# Filter_Capacitors_-_Port_A.net
KiCad netlist of a schematic drawn in Altium Designer
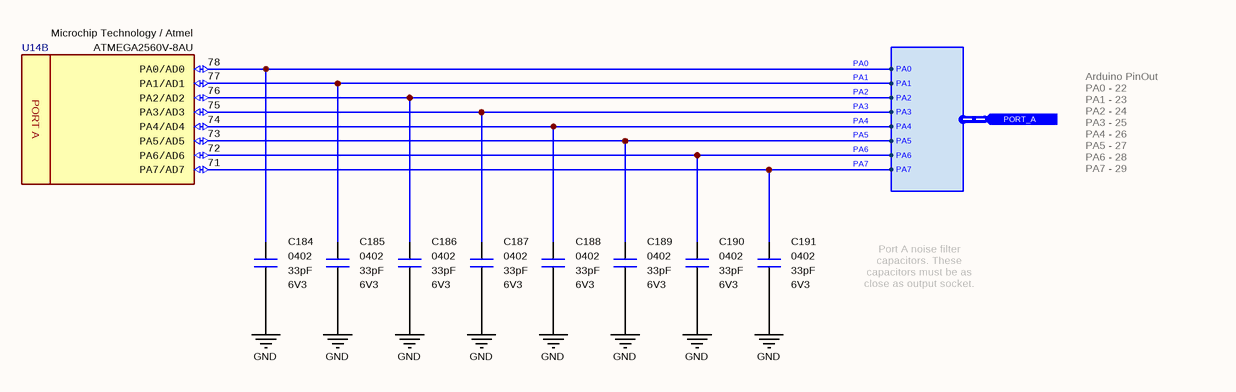
[diagram p0: Filter Capacitors - Port A.SchDoc]

(export (version "E")
  (design (tool "Eeschema 10.0.6"))
  (components
    (comp (ref "C184")
      (value "33pF")
      (footprint "CAPACITOR_0402")
      (description "Capacitor - 33pF [0402] (Ceramic)")
      (fields
        (field (name "TOLERANCE") "10%")
        (field (name "CASE") "0402")
        (field (name "VOLTAGE") "6V3")
        (field (name "MANUFACTURER PART NUMBER") "C0402C330J9RACAUTO")
      )
      (libsource (lib "Ovoo_Library") (part "Capacitor - 33pF [0402-6V3]"))
    )
    (comp (ref "C185")
      (value "33pF")
      (footprint "CAPACITOR_0402")
      (description "Capacitor - 33pF [0402] (Ceramic)")
      (fields
        (field (name "TOLERANCE") "10%")
        (field (name "CASE") "0402")
        (field (name "VOLTAGE") "6V3")
        (field (name "MANUFACTURER PART NUMBER") "C0402C330J9RACAUTO")
      )
      (libsource (lib "Ovoo_Library") (part "Capacitor - 33pF [0402-6V3]"))
    )
    (comp (ref "C186")
      (value "33pF")
      (footprint "CAPACITOR_0402")
      (description "Capacitor - 33pF [0402] (Ceramic)")
      (fields
        (field (name "TOLERANCE") "10%")
        (field (name "CASE") "0402")
        (field (name "VOLTAGE") "6V3")
        (field (name "MANUFACTURER PART NUMBER") "C0402C330J9RACAUTO")
      )
      (libsource (lib "Ovoo_Library") (part "Capacitor - 33pF [0402-6V3]"))
    )
    (comp (ref "C187")
      (value "33pF")
      (footprint "CAPACITOR_0402")
      (description "Capacitor - 33pF [0402] (Ceramic)")
      (fields
        (field (name "TOLERANCE") "10%")
        (field (name "CASE") "0402")
        (field (name "VOLTAGE") "6V3")
        (field (name "MANUFACTURER PART NUMBER") "C0402C330J9RACAUTO")
      )
      (libsource (lib "Ovoo_Library") (part "Capacitor - 33pF [0402-6V3]"))
    )
    (comp (ref "C188")
      (value "33pF")
      (footprint "CAPACITOR_0402")
      (description "Capacitor - 33pF [0402] (Ceramic)")
      (fields
        (field (name "TOLERANCE") "10%")
        (field (name "CASE") "0402")
        (field (name "VOLTAGE") "6V3")
        (field (name "MANUFACTURER PART NUMBER") "C0402C330J9RACAUTO")
      )
      (libsource (lib "Ovoo_Library") (part "Capacitor - 33pF [0402-6V3]"))
    )
    (comp (ref "C189")
      (value "33pF")
      (footprint "CAPACITOR_0402")
      (description "Capacitor - 33pF [0402] (Ceramic)")
      (fields
        (field (name "TOLERANCE") "10%")
        (field (name "CASE") "0402")
        (field (name "VOLTAGE") "6V3")
        (field (name "MANUFACTURER PART NUMBER") "C0402C330J9RACAUTO")
      )
      (libsource (lib "Ovoo_Library") (part "Capacitor - 33pF [0402-6V3]"))
    )
    (comp (ref "C190")
      (value "33pF")
      (footprint "CAPACITOR_0402")
      (description "Capacitor - 33pF [0402] (Ceramic)")
      (fields
        (field (name "TOLERANCE") "10%")
        (field (name "CASE") "0402")
        (field (name "VOLTAGE") "6V3")
        (field (name "MANUFACTURER PART NUMBER") "C0402C330J9RACAUTO")
      )
      (libsource (lib "Ovoo_Library") (part "Capacitor - 33pF [0402-6V3]"))
    )
    (comp (ref "C191")
      (value "33pF")
      (footprint "CAPACITOR_0402")
      (description "Capacitor - 33pF [0402] (Ceramic)")
      (fields
        (field (name "TOLERANCE") "10%")
        (field (name "CASE") "0402")
        (field (name "VOLTAGE") "6V3")
        (field (name "MANUFACTURER PART NUMBER") "C0402C330J9RACAUTO")
      )
      (libsource (lib "Ovoo_Library") (part "Capacitor - 33pF [0402-6V3]"))
    )
    (comp (ref "U14")
      (value "8-bit MicroController")
      (footprint "TQFP100")
      (description "8-bit Microcontrollers - MCU 256kB Flash 4kB EEPROM 86 I/O Pins")
      (fields
        (field (name "MANUFACTURER PART NUMBER") "ATMEGA2560V-8AU")
        (field (name "MANUFACTURER NAME") "Microchip Technology / Atmel")
      )
      (libsource (lib "Ovoo_Library") (part "IC - ATMEGA2560V-8AU"))
    )
  )
  (nets
    (net (code "2") (name "/PA0") (class "Default")
      (node (ref "C184") (pin "2") (pinfunction "2_2") (pintype "passive"))
      (node (ref "U14") (pin "78") (pinfunction "PA0/AD0_78") (pintype "bidirectional"))
    )
    (net (code "3") (name "/PA1") (class "Default")
      (node (ref "C185") (pin "2") (pinfunction "2_2") (pintype "passive"))
      (node (ref "U14") (pin "77") (pinfunction "PA1/AD1_77") (pintype "bidirectional"))
    )
    (net (code "4") (name "/PA2") (class "Default")
      (node (ref "C186") (pin "2") (pinfunction "2_2") (pintype "passive"))
      (node (ref "U14") (pin "76") (pinfunction "PA2/AD2_76") (pintype "bidirectional"))
    )
    (net (code "5") (name "/PA3") (class "Default")
      (node (ref "C187") (pin "2") (pinfunction "2_2") (pintype "passive"))
      (node (ref "U14") (pin "75") (pinfunction "PA3/AD3_75") (pintype "bidirectional"))
    )
    (net (code "6") (name "/PA4") (class "Default")
      (node (ref "C188") (pin "2") (pinfunction "2_2") (pintype "passive"))
      (node (ref "U14") (pin "74") (pinfunction "PA4/AD4_74") (pintype "bidirectional"))
    )
    (net (code "7") (name "/PA5") (class "Default")
      (node (ref "C189") (pin "2") (pinfunction "2_2") (pintype "passive"))
      (node (ref "U14") (pin "73") (pinfunction "PA5/AD5_73") (pintype "bidirectional"))
    )
    (net (code "8") (name "/PA6") (class "Default")
      (node (ref "C190") (pin "2") (pinfunction "2_2") (pintype "passive"))
      (node (ref "U14") (pin "72") (pinfunction "PA6/AD6_72") (pintype "bidirectional"))
    )
    (net (code "9") (name "/PA7") (class "Default")
      (node (ref "C191") (pin "2") (pinfunction "2_2") (pintype "passive"))
      (node (ref "U14") (pin "71") (pinfunction "PA7/AD7_71") (pintype "bidirectional"))
    )
    (net (code "11") (name "GND") (class "Default")
      (node (ref "C184") (pin "1") (pinfunction "1_1") (pintype "passive"))
      (node (ref "C185") (pin "1") (pinfunction "1_1") (pintype "passive"))
      (node (ref "C186") (pin "1") (pinfunction "1_1") (pintype "passive"))
      (node (ref "C187") (pin "1") (pinfunction "1_1") (pintype "passive"))
      (node (ref "C188") (pin "1") (pinfunction "1_1") (pintype "passive"))
      (node (ref "C189") (pin "1") (pinfunction "1_1") (pintype "passive"))
      (node (ref "C190") (pin "1") (pinfunction "1_1") (pintype "passive"))
      (node (ref "C191") (pin "1") (pinfunction "1_1") (pintype "passive"))
    )
  )
)
